# ServoController.net
KiCad netlist of a schematic drawn in EAGLE
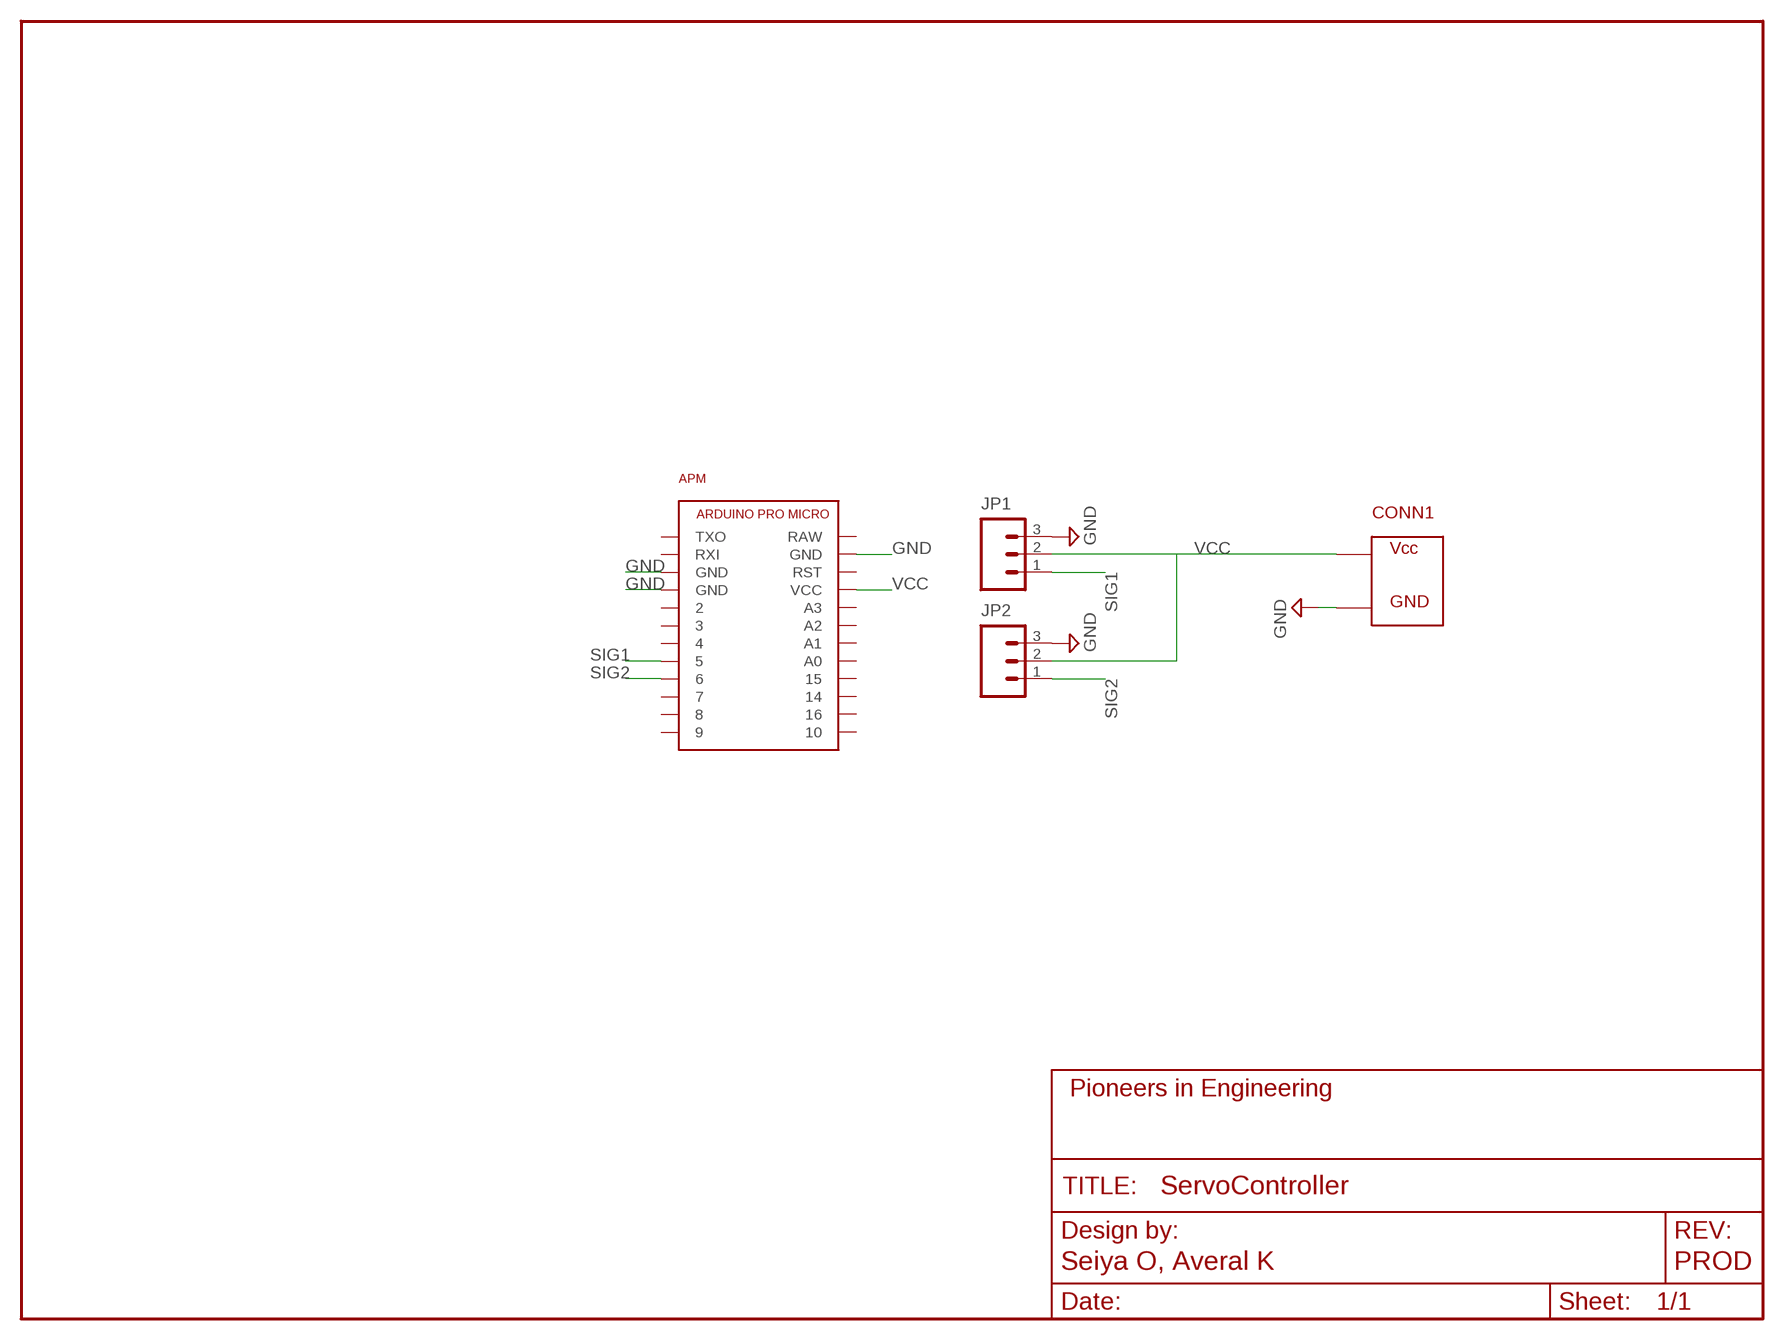
[diagram p0: schematic, sheet 1]

(export (version "E")
  (design (tool "Eeschema 10.0.6"))
  (components
    (comp (ref "APM")
      (value "ARDUINO_PRO_MICRO")
      (footprint "eagle-import:ARDUINO_PRO_MICRO")
      (fields
        (field (name "DISTRIBUTOR_PART_NUMBER") "32284746884")
        (field (name "MANUFACTURER") "Feiyang electronics")
      )
      (libsource (lib "eagle-import") (part "ARDUINO_PRO_MICRO"))
    )
    (comp (ref "CONN1")
      (value "ATX")
      (footprint "eagle-import:ATX")
      (libsource (lib "eagle-import") (part "ATX"))
    )
    (comp (ref "JP1")
      (value "M031X03-MTA")
      (footprint "eagle-import:1X03-MTA")
      (libsource (lib "eagle-import") (part "M031X03-MTA"))
    )
    (comp (ref "JP2")
      (value "M031X03-MTA")
      (footprint "eagle-import:1X03-MTA")
      (libsource (lib "eagle-import") (part "M031X03-MTA"))
    )
  )
  (nets
    (net (code "1") (name "/SIG1") (class "Default")
      (node (ref "APM") (pin "5") (pinfunction "5_5") (pintype "bidirectional"))
      (node (ref "JP1") (pin "1") (pinfunction "1_1") (pintype "passive"))
    )
    (net (code "2") (name "/SIG2") (class "Default")
      (node (ref "APM") (pin "6") (pinfunction "6_6") (pintype "bidirectional"))
      (node (ref "JP2") (pin "1") (pinfunction "1_1") (pintype "passive"))
    )
    (net (code "3") (name "/VCC") (class "Default")
      (node (ref "APM") (pin "VCC") (pinfunction "VCC_VCC") (pintype "bidirectional"))
      (node (ref "CONN1") (pin "P$1") (pinfunction "P$1_P$1") (pintype "power_in"))
      (node (ref "JP1") (pin "2") (pinfunction "2_2") (pintype "passive"))
      (node (ref "JP2") (pin "2") (pinfunction "2_2") (pintype "passive"))
    )
    (net (code "4") (name "GND") (class "Default")
      (node (ref "APM") (pin "GND@0") (pinfunction "GND_GND@0") (pintype "bidirectional"))
      (node (ref "APM") (pin "GND@1") (pinfunction "GND_GND@1") (pintype "bidirectional"))
      (node (ref "APM") (pin "GND@2") (pinfunction "GND_GND@2") (pintype "bidirectional"))
      (node (ref "CONN1") (pin "P$2") (pinfunction "P$2_P$2") (pintype "power_in"))
      (node (ref "JP1") (pin "3") (pinfunction "3_3") (pintype "passive"))
      (node (ref "JP2") (pin "3") (pinfunction "3_3") (pintype "passive"))
    )
    (net (code "5") (name "unconnected-(APM-Pad2)") (class "Default")
      (node (ref "APM") (pin "2") (pinfunction "2_2") (pintype "bidirectional"))
    )
    (net (code "6") (name "unconnected-(APM-Pad3)") (class "Default")
      (node (ref "APM") (pin "3") (pinfunction "3_3") (pintype "bidirectional"))
    )
    (net (code "7") (name "unconnected-(APM-Pad4)") (class "Default")
      (node (ref "APM") (pin "4") (pinfunction "4_4") (pintype "bidirectional"))
    )
    (net (code "8") (name "unconnected-(APM-Pad7)") (class "Default")
      (node (ref "APM") (pin "7") (pinfunction "7_7") (pintype "bidirectional"))
    )
    (net (code "9") (name "unconnected-(APM-Pad8)") (class "Default")
      (node (ref "APM") (pin "8") (pinfunction "8_8") (pintype "bidirectional"))
    )
    (net (code "10") (name "unconnected-(APM-Pad9)") (class "Default")
      (node (ref "APM") (pin "9") (pinfunction "9_9") (pintype "bidirectional"))
    )
    (net (code "11") (name "unconnected-(APM-Pad10)") (class "Default")
      (node (ref "APM") (pin "10") (pinfunction "10_10") (pintype "bidirectional"))
    )
    (net (code "12") (name "unconnected-(APM-Pad14)") (class "Default")
      (node (ref "APM") (pin "14") (pinfunction "14_14") (pintype "bidirectional"))
    )
    (net (code "13") (name "unconnected-(APM-Pad15)") (class "Default")
      (node (ref "APM") (pin "15") (pinfunction "15_15") (pintype "bidirectional"))
    )
    (net (code "14") (name "unconnected-(APM-Pad16)") (class "Default")
      (node (ref "APM") (pin "16") (pinfunction "16_16") (pintype "bidirectional"))
    )
    (net (code "15") (name "unconnected-(APM-PadA0)") (class "Default")
      (node (ref "APM") (pin "A0") (pinfunction "A0_A0") (pintype "bidirectional"))
    )
    (net (code "16") (name "unconnected-(APM-PadA1)") (class "Default")
      (node (ref "APM") (pin "A1") (pinfunction "A1_A1") (pintype "bidirectional"))
    )
    (net (code "17") (name "unconnected-(APM-PadA2)") (class "Default")
      (node (ref "APM") (pin "A2") (pinfunction "A2_A2") (pintype "bidirectional"))
    )
    (net (code "18") (name "unconnected-(APM-PadA3)") (class "Default")
      (node (ref "APM") (pin "A3") (pinfunction "A3_A3") (pintype "bidirectional"))
    )
    (net (code "19") (name "unconnected-(APM-PadRAW)") (class "Default")
      (node (ref "APM") (pin "RAW") (pinfunction "RAW_RAW") (pintype "bidirectional"))
    )
    (net (code "20") (name "unconnected-(APM-PadRST)") (class "Default")
      (node (ref "APM") (pin "RST") (pinfunction "RST_RST") (pintype "bidirectional"))
    )
    (net (code "21") (name "unconnected-(APM-PadRXI)") (class "Default")
      (node (ref "APM") (pin "RXI") (pinfunction "RXI_RXI") (pintype "bidirectional"))
    )
    (net (code "22") (name "unconnected-(APM-PadTXO)") (class "Default")
      (node (ref "APM") (pin "TXO") (pinfunction "TXO_TXO") (pintype "bidirectional"))
    )
  )
)
